# ADC_GPIO_Expander.net
KiCad netlist of a schematic drawn in Altium Designer
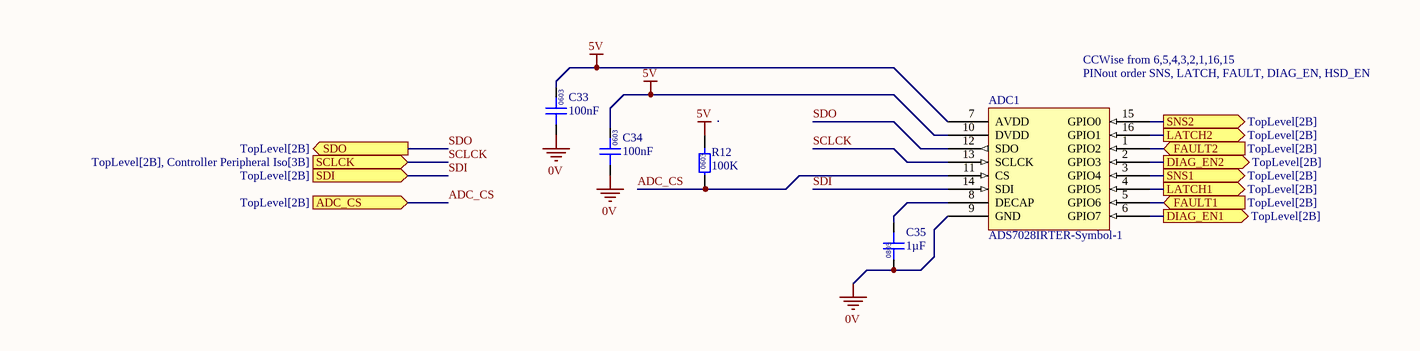
[diagram p0: ADC GPIO Expander.SchDoc]

(export (version "E")
  (design (tool "Eeschema 10.0.6"))
  (components
    (comp (ref "ADC1")
      (value "ADS7028IRTER-Symbol-1")
      (footprint "WFQN-16")
      (description "IC ADC 12BIT SAR 16WQFN")
      (fields (field (name "PART NUMBER") "ADS7028IRTER") (field (name "MANUFACTURER") "Texas Instruments"))
      (libsource (lib "ts_standard_library") (part "ADS7028IRTER"))
    )
    (comp (ref "C33")
      (value "100nF")
      (footprint "0603")
      (fields
        (field (name "PART NUMBER") "GCM188L81H104KA57D")
        (field (name "MANUFACTURER") "muRata")
        (field (name "TOLERANCE") "±10%")
      )
      (libsource (lib "ts_standard_library") (part "Capacitor 0603"))
    )
    (comp (ref "C34")
      (value "100nF")
      (footprint "0603")
      (fields
        (field (name "PART NUMBER") "GCM188L81H104KA57D")
        (field (name "MANUFACTURER") "muRata")
        (field (name "TOLERANCE") "±10%")
      )
      (libsource (lib "ts_standard_library") (part "Capacitor 0603"))
    )
    (comp (ref "C35")
      (value "1µF")
      (footprint "0805")
      (fields
        (field (name "PART NUMBER") "GCM21BR71H105KA03L")
        (field (name "MANUFACTURER") "muRata")
        (field (name "TOLERANCE") "±10%")
      )
      (libsource (lib "ts_standard_library") (part "Capacitor 0805"))
    )
    (comp (ref "R12")
      (value "100K")
      (footprint "0603")
      (fields
        (field (name "PART NUMBER") "RC0603FR-07100KL")
        (field (name "MANUFACTURER") "YAGEO")
        (field (name "TOLERANCE") "0.01")
      )
      (libsource (lib "ts_standard_library") (part "Resistor 0603"))
    )
  )
  (nets
    (net (code "1") (name "/ADC_CS") (class "Default")
      (node (ref "ADC1") (pin "11") (pinfunction "CS_11") (pintype "input"))
      (node (ref "R12") (pin "1") (pinfunction "1_1") (pintype "passive"))
    )
    (net (code "2") (name "/DIAG_EN1") (class "Default")
      (node (ref "ADC1") (pin "6") (pinfunction "GPIO7_6") (pintype "input"))
    )
    (net (code "3") (name "/DIAG_EN2") (class "Default")
      (node (ref "ADC1") (pin "2") (pinfunction "GPIO3_2") (pintype "input"))
    )
    (net (code "4") (name "/FAULT1") (class "Default")
      (node (ref "ADC1") (pin "5") (pinfunction "GPIO6_5") (pintype "input"))
    )
    (net (code "5") (name "/FAULT2") (class "Default")
      (node (ref "ADC1") (pin "1") (pinfunction "GPIO2_1") (pintype "input"))
    )
    (net (code "6") (name "/LATCH1") (class "Default")
      (node (ref "ADC1") (pin "4") (pinfunction "GPIO5_4") (pintype "input"))
    )
    (net (code "7") (name "/LATCH2") (class "Default")
      (node (ref "ADC1") (pin "16") (pinfunction "GPIO1_16") (pintype "input"))
    )
    (net (code "8") (name "/SCLCK") (class "Default")
      (node (ref "ADC1") (pin "13") (pinfunction "SCLCK_13") (pintype "input"))
    )
    (net (code "9") (name "/SDI") (class "Default")
      (node (ref "ADC1") (pin "14") (pinfunction "SDI_14") (pintype "input"))
    )
    (net (code "10") (name "/SDO") (class "Default")
      (node (ref "ADC1") (pin "12") (pinfunction "SDO_12") (pintype "output"))
    )
    (net (code "11") (name "/SNS1") (class "Default")
      (node (ref "ADC1") (pin "3") (pinfunction "GPIO4_3") (pintype "input"))
    )
    (net (code "12") (name "/SNS2") (class "Default")
      (node (ref "ADC1") (pin "15") (pinfunction "GPIO0_15") (pintype "input"))
    )
    (net (code "13") (name "0V") (class "Default")
      (node (ref "ADC1") (pin "9") (pinfunction "GND_9") (pintype "power_in"))
      (node (ref "C33") (pin "1") (pinfunction "1_1") (pintype "passive"))
      (node (ref "C34") (pin "1") (pinfunction "1_1") (pintype "passive"))
      (node (ref "C35") (pin "1") (pinfunction "1_1") (pintype "passive"))
    )
    (net (code "14") (name "5V") (class "Default")
      (node (ref "ADC1") (pin "10") (pinfunction "DVDD_10") (pintype "power_in"))
      (node (ref "ADC1") (pin "7") (pinfunction "AVDD_7") (pintype "power_in"))
      (node (ref "C33") (pin "2") (pinfunction "2_2") (pintype "passive"))
      (node (ref "C34") (pin "2") (pinfunction "2_2") (pintype "passive"))
      (node (ref "R12") (pin "2") (pinfunction "2_2") (pintype "passive"))
    )
    (net (code "15") (name "Net-(ADC1-DECAP)") (class "Default")
      (node (ref "ADC1") (pin "8") (pinfunction "DECAP_8") (pintype "power_in"))
      (node (ref "C35") (pin "2") (pinfunction "2_2") (pintype "passive"))
    )
  )
)
